# RICK_TNY_00.net
KiCad netlist of a schematic drawn in Altium Designer
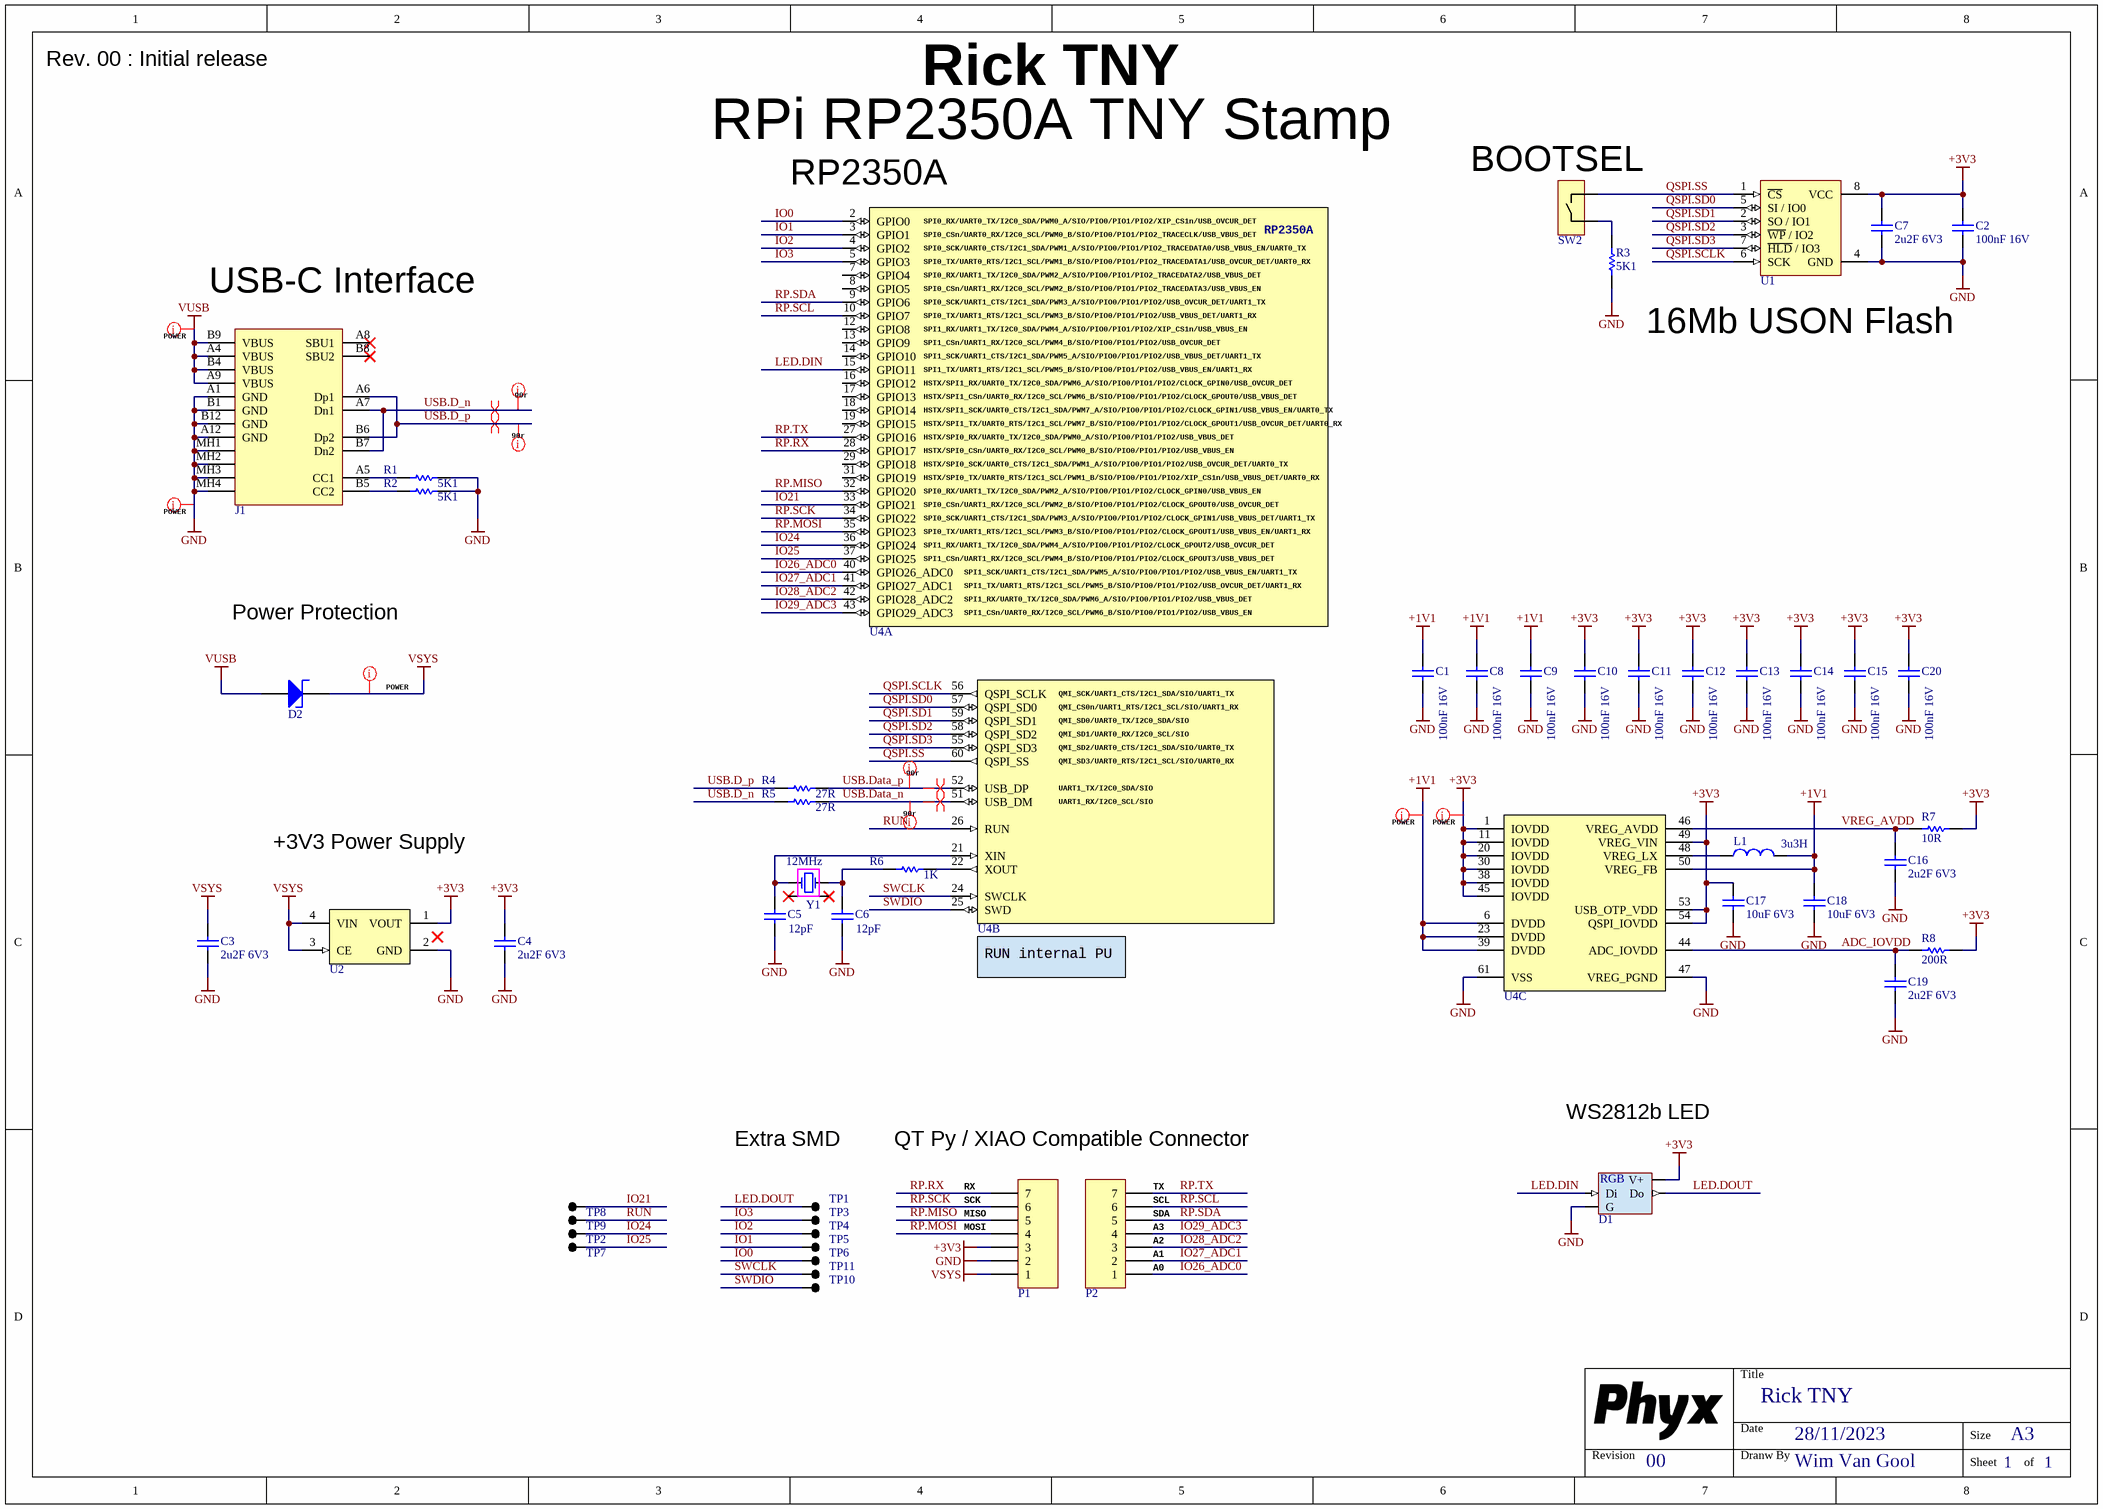
[diagram p0: RICK_TNY_00.SchDoc]

(export (version "E")
  (design (tool "Eeschema 10.0.6"))
  (components
    (comp (ref "C1")
      (value "100nF 16V")
      (footprint "C0402")
      (description "Capacitor Ceramic")
      (fields (field (name "Comment") "CAP_CERAMIC"))
      (libsource (lib "Phyx_Components") (part "CAP_CERAMIC"))
    )
    (comp (ref "C2")
      (value "100nF 16V")
      (footprint "C0402")
      (description "Capacitor Ceramic")
      (fields (field (name "Comment") "CAP_CERAMIC"))
      (libsource (lib "Phyx_Components") (part "CAP_CERAMIC"))
    )
    (comp (ref "C3")
      (value "2u2F 6V3")
      (footprint "C0402")
      (description "Capacitor Ceramic")
      (fields (field (name "Comment") "CAP_CERAMIC"))
      (libsource (lib "Phyx_Components") (part "CAP_CERAMIC"))
    )
    (comp (ref "C4")
      (value "2u2F 6V3")
      (footprint "C0402")
      (description "Capacitor Ceramic")
      (fields (field (name "Comment") "CAP_CERAMIC"))
      (libsource (lib "Phyx_Components") (part "CAP_CERAMIC"))
    )
    (comp (ref "C5")
      (value "12pF")
      (footprint "C0402")
      (description "CAP # 12pF 50V 0402")
      (fields (field (name "Comment") "CAP_CERAMIC"))
      (libsource (lib "Phyx_Components") (part "CAP_CERAMIC"))
    )
    (comp (ref "C6")
      (value "12pF")
      (footprint "C0402")
      (description "CAP # 12pF 50V 0402")
      (fields (field (name "Comment") "CAP_CERAMIC"))
      (libsource (lib "Phyx_Components") (part "CAP_CERAMIC"))
    )
    (comp (ref "C7")
      (value "2u2F 6V3")
      (footprint "C0402")
      (description "Capacitor Ceramic")
      (fields (field (name "Comment") "CAP_CERAMIC"))
      (libsource (lib "Phyx_Components") (part "CAP_CERAMIC"))
    )
    (comp (ref "C8")
      (value "100nF 16V")
      (footprint "C0402")
      (description "Capacitor Ceramic")
      (fields (field (name "Comment") "CAP_CERAMIC"))
      (libsource (lib "Phyx_Components") (part "CAP_CERAMIC"))
    )
    (comp (ref "C9")
      (value "100nF 16V")
      (footprint "C0402")
      (description "Capacitor Ceramic")
      (fields (field (name "Comment") "CAP_CERAMIC"))
      (libsource (lib "Phyx_Components") (part "CAP_CERAMIC"))
    )
    (comp (ref "C10")
      (value "100nF 16V")
      (footprint "C0402")
      (description "Capacitor Ceramic")
      (fields (field (name "Comment") "CAP_CERAMIC"))
      (libsource (lib "Phyx_Components") (part "CAP_CERAMIC"))
    )
    (comp (ref "C11")
      (value "100nF 16V")
      (footprint "C0402")
      (description "Capacitor Ceramic")
      (fields (field (name "Comment") "CAP_CERAMIC"))
      (libsource (lib "Phyx_Components") (part "CAP_CERAMIC"))
    )
    (comp (ref "C12")
      (value "100nF 16V")
      (footprint "C0402")
      (description "Capacitor Ceramic")
      (fields (field (name "Comment") "CAP_CERAMIC"))
      (libsource (lib "Phyx_Components") (part "CAP_CERAMIC"))
    )
    (comp (ref "C13")
      (value "100nF 16V")
      (footprint "C0402")
      (description "Capacitor Ceramic")
      (fields (field (name "Comment") "CAP_CERAMIC"))
      (libsource (lib "Phyx_Components") (part "CAP_CERAMIC"))
    )
    (comp (ref "C14")
      (value "100nF 16V")
      (footprint "C0402")
      (description "Capacitor Ceramic")
      (fields (field (name "Comment") "CAP_CERAMIC"))
      (libsource (lib "Phyx_Components") (part "CAP_CERAMIC"))
    )
    (comp (ref "C15")
      (value "100nF 16V")
      (footprint "C0402")
      (description "Capacitor Ceramic")
      (fields (field (name "Comment") "CAP_CERAMIC"))
      (libsource (lib "Phyx_Components") (part "CAP_CERAMIC"))
    )
    (comp (ref "C16")
      (value "2u2F 6V3")
      (footprint "C0402")
      (description "Capacitor Ceramic")
      (fields (field (name "Comment") "CAP_CERAMIC"))
      (libsource (lib "Phyx_Components") (part "CAP_CERAMIC"))
    )
    (comp (ref "C17")
      (value "10uF 6V3")
      (footprint "C0402")
      (description "Capacitor Ceramic")
      (fields (field (name "Comment") "CAP_CERAMIC"))
      (libsource (lib "Phyx_Components") (part "CAP_CERAMIC"))
    )
    (comp (ref "C18")
      (value "10uF 6V3")
      (footprint "C0402")
      (description "Capacitor Ceramic")
      (fields (field (name "Comment") "CAP_CERAMIC"))
      (libsource (lib "Phyx_Components") (part "CAP_CERAMIC"))
    )
    (comp (ref "C19")
      (value "2u2F 6V3")
      (footprint "C0402")
      (description "Capacitor Ceramic")
      (fields (field (name "Comment") "CAP_CERAMIC"))
      (libsource (lib "Phyx_Components") (part "CAP_CERAMIC"))
    )
    (comp (ref "C20")
      (value "100nF 16V")
      (footprint "C0402")
      (description "Capacitor Ceramic")
      (fields (field (name "Comment") "CAP_CERAMIC"))
      (libsource (lib "Phyx_Components") (part "CAP_CERAMIC"))
    )
    (comp (ref "D1")
      (value "WS2812 based digital RGB LED 1010 package")
      (footprint "LED_1010_WS2812B")
      (description "=Description")
      (libsource (lib "Phyx_Components") (part "LED_RGB_WS2812B_1010"))
    )
    (comp (ref "D2")
      (value "40V 1A 550mV@700mA 0603 Schottky")
      (footprint "ON_DSN2")
      (description "=Description")
      (libsource (lib "Phyx_Components") (part "Schottky_AC"))
    )
    (comp (ref "J1")
      (value "USB 2.0 C Reversible Receptacle Horizontal full SMD")
      (footprint "XUNPU-TYPEC-304S-ACP16")
      (libsource (lib "Phyx_Components") (part "USB_C_16_4"))
    )
    (comp (ref "L1")
      (value "3u3H")
      (footprint "L0805")
      (fields (field (name "Comment") "LQM21PN3R3MGRD"))
      (libsource (lib "Phyx_Components") (part "INDUCTOR"))
    )
    (comp (ref "P1") (value "Header 7") (footprint "HDR1X7") (libsource (lib "") (part "Header 7_1")))
    (comp (ref "P2")
      (value "Header 7")
      (footprint "HDR1X7")
      (libsource (lib "Phyx_Components") (part "Header 7"))
    )
    (comp (ref "R1")
      (value "5K1")
      (footprint "R0402")
      (fields (field (name "Comment") "RESISTOR"))
      (libsource (lib "Phyx_Components") (part "RESISTOR"))
    )
    (comp (ref "R2")
      (value "5K1")
      (footprint "R0402")
      (fields (field (name "Comment") "RESISTOR"))
      (libsource (lib "Phyx_Components") (part "RESISTOR"))
    )
    (comp (ref "R3")
      (value "5K1")
      (footprint "R0402")
      (fields (field (name "Comment") "RESISTOR"))
      (libsource (lib "Phyx_Components") (part "RESISTOR"))
    )
    (comp (ref "R4")
      (value "27R")
      (footprint "R0402")
      (fields (field (name "Comment") "RESISTOR"))
      (libsource (lib "Phyx_Components") (part "RESISTOR"))
    )
    (comp (ref "R5")
      (value "27R")
      (footprint "R0402")
      (fields (field (name "Comment") "RESISTOR"))
      (libsource (lib "Phyx_Components") (part "RESISTOR"))
    )
    (comp (ref "R6")
      (value "1K")
      (footprint "R0402")
      (fields (field (name "Comment") "RESISTOR"))
      (libsource (lib "Phyx_Components") (part "RESISTOR"))
    )
    (comp (ref "R7")
      (value "10R")
      (footprint "R0402")
      (fields (field (name "Comment") "RESISTOR"))
      (libsource (lib "Phyx_Components") (part "RESISTOR"))
    )
    (comp (ref "R8")
      (value "200R")
      (footprint "R0402")
      (fields (field (name "Comment") "RESISTOR"))
      (libsource (lib "Phyx_Components") (part "RESISTOR"))
    )
    (comp (ref "SW2")
      (value "TS24CA RA Tactile Switch 12V 50mA")
      (footprint "SHOU_HAN_TS24CA")
      (libsource (lib "Phyx_Components") (part "SW_TACT"))
    )
    (comp (ref "TP1")
      (value "TEST_PAD")
      (footprint "TP_0.4mm")
      (libsource (lib "Phyx_Components") (part "TEST_PAD"))
    )
    (comp (ref "TP2")
      (value "TEST_PAD")
      (footprint "TP_0.4mm")
      (libsource (lib "Phyx_Components") (part "TEST_PAD"))
    )
    (comp (ref "TP3")
      (value "TEST_PAD")
      (footprint "TP_0.4mm")
      (libsource (lib "Phyx_Components") (part "TEST_PAD"))
    )
    (comp (ref "TP4")
      (value "TEST_PAD")
      (footprint "TP_0.4mm")
      (libsource (lib "Phyx_Components") (part "TEST_PAD"))
    )
    (comp (ref "TP5")
      (value "TEST_PAD")
      (footprint "TP_0.4mm")
      (libsource (lib "Phyx_Components") (part "TEST_PAD"))
    )
    (comp (ref "TP6")
      (value "TEST_PAD")
      (footprint "TP_0.4mm")
      (libsource (lib "Phyx_Components") (part "TEST_PAD"))
    )
    (comp (ref "TP7")
      (value "TEST_PAD")
      (footprint "TP_0.4mm")
      (libsource (lib "Phyx_Components") (part "TEST_PAD"))
    )
    (comp (ref "TP8")
      (value "TEST_PAD")
      (footprint "TP_0.4mm")
      (libsource (lib "Phyx_Components") (part "TEST_PAD"))
    )
    (comp (ref "TP9")
      (value "TEST_PAD")
      (footprint "TP_0.4mm")
      (libsource (lib "Phyx_Components") (part "TEST_PAD"))
    )
    (comp (ref "TP10")
      (value "TEST_PAD")
      (footprint "TP_0.4mm")
      (libsource (lib "Phyx_Components") (part "TEST_PAD"))
    )
    (comp (ref "TP11")
      (value "TEST_PAD")
      (footprint "TP_0.4mm")
      (libsource (lib "Phyx_Components") (part "TEST_PAD"))
    )
    (comp (ref "U1")
      (value "16Mb 3V3 133MHz SPI Flash DFN2x3 GD25Q16EEIGR")
      (footprint "USON_8_0.5_2x3")
      (libsource (lib "Phyx_Components") (part "AT25SFxx"))
    )
    (comp (ref "U2")
      (value "3V3 LDO 500mA 150mV")
      (footprint "DFNWB_1.0x1.0")
      (description "=Designator")
      (libsource (lib "Phyx_Components") (part "LDO_OGEI"))
    )
    (comp (ref "U4")
      (value "RPi RP2350 QFN60 2xM33 ext Flash")
      (footprint "RPI_QFN60_0.4_7x7")
      (description "=Description")
      (libsource (lib "Phyx_Components") (part "RPI_RP2350A"))
    )
    (comp (ref "Y1")
      (value "12MHz")
      (footprint "XTAL_2520")
      (description "Crystal Oscillator 4pin casing")
      (fields (field (name "Comment") "12MHz 2520 12pF ±10ppm ±30ppm"))
      (libsource (lib "Phyx_Components") (part "XTAL_4"))
    )
  )
  (nets
    (net (code "1") (name "+1V1") (class "Default")
      (node (ref "C1") (pin "1") (pinfunction "1_1") (pintype "passive"))
      (node (ref "C18") (pin "1") (pinfunction "1_1") (pintype "passive"))
      (node (ref "C8") (pin "1") (pinfunction "1_1") (pintype "passive"))
      (node (ref "C9") (pin "1") (pinfunction "1_1") (pintype "passive"))
      (node (ref "L1") (pin "2") (pinfunction "2_2") (pintype "passive"))
      (node (ref "U4") (pin "23") (pinfunction "DVDD_23") (pintype "power_in"))
      (node (ref "U4") (pin "39") (pinfunction "DVDD_39") (pintype "power_in"))
      (node (ref "U4") (pin "50") (pinfunction "VREG_FB_50") (pintype "power_in"))
      (node (ref "U4") (pin "6") (pinfunction "DVDD_6") (pintype "power_in"))
    )
    (net (code "2") (name "+3V3") (class "Default")
      (node (ref "C10") (pin "1") (pinfunction "1_1") (pintype "passive"))
      (node (ref "C11") (pin "1") (pinfunction "1_1") (pintype "passive"))
      (node (ref "C12") (pin "1") (pinfunction "1_1") (pintype "passive"))
      (node (ref "C13") (pin "1") (pinfunction "1_1") (pintype "passive"))
      (node (ref "C14") (pin "1") (pinfunction "1_1") (pintype "passive"))
      (node (ref "C15") (pin "1") (pinfunction "1_1") (pintype "passive"))
      (node (ref "C17") (pin "1") (pinfunction "1_1") (pintype "passive"))
      (node (ref "C2") (pin "1") (pinfunction "1_1") (pintype "passive"))
      (node (ref "C20") (pin "1") (pinfunction "1_1") (pintype "passive"))
      (node (ref "C4") (pin "1") (pinfunction "1_1") (pintype "passive"))
      (node (ref "C7") (pin "1") (pinfunction "1_1") (pintype "passive"))
      (node (ref "D1") (pin "2") (pinfunction "V+_2") (pintype "power_in"))
      (node (ref "P1") (pin "3") (pinfunction "3_3") (pintype "passive"))
      (node (ref "R7") (pin "1") (pinfunction "1_1") (pintype "passive"))
      (node (ref "R8") (pin "1") (pinfunction "1_1") (pintype "passive"))
      (node (ref "U1") (pin "8") (pinfunction "VCC_8") (pintype "power_in"))
      (node (ref "U2") (pin "1") (pinfunction "VOUT_1") (pintype "power_in"))
      (node (ref "U4") (pin "1") (pinfunction "IOVDD_1") (pintype "power_in"))
      (node (ref "U4") (pin "11") (pinfunction "IOVDD_11") (pintype "power_in"))
      (node (ref "U4") (pin "20") (pinfunction "IOVDD_20") (pintype "power_in"))
      (node (ref "U4") (pin "30") (pinfunction "IOVDD_30") (pintype "power_in"))
      (node (ref "U4") (pin "38") (pinfunction "IOVDD_38") (pintype "power_in"))
      (node (ref "U4") (pin "45") (pinfunction "IOVDD_45") (pintype "power_in"))
      (node (ref "U4") (pin "49") (pinfunction "VREG_VIN_49") (pintype "power_in"))
      (node (ref "U4") (pin "53") (pinfunction "USB_OTP_VDD_53") (pintype "power_in"))
      (node (ref "U4") (pin "54") (pinfunction "QSPI_IOVDD_54") (pintype "power_in"))
    )
    (net (code "3") (name "/ADC_IOVDD") (class "Default")
      (node (ref "C19") (pin "1") (pinfunction "1_1") (pintype "passive"))
      (node (ref "R8") (pin "2") (pinfunction "2_2") (pintype "passive"))
      (node (ref "U4") (pin "44") (pinfunction "ADC_IOVDD_44") (pintype "power_in"))
    )
    (net (code "4") (name "/IO0") (class "Default")
      (node (ref "TP6") (pin "1") (pinfunction "1_1") (pintype "passive"))
      (node (ref "U4") (pin "2") (pinfunction "GPIO0_2") (pintype "bidirectional"))
    )
    (net (code "5") (name "/IO1") (class "Default")
      (node (ref "TP5") (pin "1") (pinfunction "1_1") (pintype "passive"))
      (node (ref "U4") (pin "3") (pinfunction "GPIO1_3") (pintype "bidirectional"))
    )
    (net (code "6") (name "/IO2") (class "Default")
      (node (ref "TP4") (pin "1") (pinfunction "1_1") (pintype "passive"))
      (node (ref "U4") (pin "4") (pinfunction "GPIO2_4") (pintype "bidirectional"))
    )
    (net (code "7") (name "/IO3") (class "Default")
      (node (ref "TP3") (pin "1") (pinfunction "1_1") (pintype "passive"))
      (node (ref "U4") (pin "5") (pinfunction "GPIO3_5") (pintype "bidirectional"))
    )
    (net (code "8") (name "/IO21") (class "Default")
      (node (ref "TP8") (pin "1") (pinfunction "1_1") (pintype "passive"))
      (node (ref "U4") (pin "33") (pinfunction "GPIO21_33") (pintype "bidirectional"))
    )
    (net (code "9") (name "/IO24") (class "Default")
      (node (ref "TP2") (pin "1") (pinfunction "1_1") (pintype "passive"))
      (node (ref "U4") (pin "36") (pinfunction "GPIO24_36") (pintype "bidirectional"))
    )
    (net (code "10") (name "/IO25") (class "Default")
      (node (ref "TP7") (pin "1") (pinfunction "1_1") (pintype "passive"))
      (node (ref "U4") (pin "37") (pinfunction "GPIO25_37") (pintype "bidirectional"))
    )
    (net (code "11") (name "/IO26_ADC0") (class "Default")
      (node (ref "P2") (pin "1") (pinfunction "1_1") (pintype "passive"))
      (node (ref "U4") (pin "40") (pinfunction "GPIO26_ADC0_40") (pintype "bidirectional"))
    )
    (net (code "12") (name "/IO27_ADC1") (class "Default")
      (node (ref "P2") (pin "2") (pinfunction "2_2") (pintype "passive"))
      (node (ref "U4") (pin "41") (pinfunction "GPIO27_ADC1_41") (pintype "bidirectional"))
    )
    (net (code "13") (name "/IO28_ADC2") (class "Default")
      (node (ref "P2") (pin "3") (pinfunction "3_3") (pintype "passive"))
      (node (ref "U4") (pin "42") (pinfunction "GPIO28_ADC2_42") (pintype "bidirectional"))
    )
    (net (code "14") (name "/IO29_ADC3") (class "Default")
      (node (ref "P2") (pin "4") (pinfunction "4_4") (pintype "passive"))
      (node (ref "U4") (pin "43") (pinfunction "GPIO29_ADC3_43") (pintype "bidirectional"))
    )
    (net (code "15") (name "/LED.DIN") (class "Default")
      (node (ref "D1") (pin "4") (pinfunction "Di_4") (pintype "input"))
      (node (ref "U4") (pin "15") (pinfunction "GPIO11_15") (pintype "bidirectional"))
    )
    (net (code "16") (name "/LED.DOUT") (class "Default")
      (node (ref "D1") (pin "1") (pinfunction "Do_1") (pintype "output"))
      (node (ref "TP1") (pin "1") (pinfunction "1_1") (pintype "passive"))
    )
    (net (code "17") (name "/QSPI.SCLK") (class "Default")
      (node (ref "U1") (pin "6") (pinfunction "SCK_6") (pintype "input"))
      (node (ref "U4") (pin "56") (pinfunction "QSPI_SCLK_56") (pintype "output"))
    )
    (net (code "18") (name "/QSPI.SD0") (class "Default")
      (node (ref "U1") (pin "5") (pinfunction "SI_/_IO0_5") (pintype "bidirectional"))
      (node (ref "U4") (pin "57") (pinfunction "QSPI_SD0_57") (pintype "bidirectional"))
    )
    (net (code "19") (name "/QSPI.SD1") (class "Default")
      (node (ref "U1") (pin "2") (pinfunction "SO_/_IO1_2") (pintype "bidirectional"))
      (node (ref "U4") (pin "59") (pinfunction "QSPI_SD1_59") (pintype "bidirectional"))
    )
    (net (code "20") (name "/QSPI.SD2") (class "Default")
      (node (ref "U1") (pin "3") (pinfunction "~{WP}_/_IO2_3") (pintype "bidirectional"))
      (node (ref "U4") (pin "58") (pinfunction "QSPI_SD2_58") (pintype "bidirectional"))
    )
    (net (code "21") (name "/QSPI.SD3") (class "Default")
      (node (ref "U1") (pin "7") (pinfunction "~{HLD}_/_IO3_7") (pintype "bidirectional"))
      (node (ref "U4") (pin "55") (pinfunction "QSPI_SD3_55") (pintype "bidirectional"))
    )
    (net (code "22") (name "/QSPI.SS") (class "Default")
      (node (ref "SW2") (pin "1") (pinfunction "1_1") (pintype "passive"))
      (node (ref "U1") (pin "1") (pinfunction "~{CS}_1") (pintype "input"))
      (node (ref "U4") (pin "60") (pinfunction "QSPI_SS_60") (pintype "output"))
    )
    (net (code "23") (name "/RP.MISO") (class "Default")
      (node (ref "P1") (pin "5") (pinfunction "5_5") (pintype "passive"))
      (node (ref "U4") (pin "32") (pinfunction "GPIO20_32") (pintype "bidirectional"))
    )
    (net (code "24") (name "/RP.MOSI") (class "Default")
      (node (ref "P1") (pin "4") (pinfunction "4_4") (pintype "passive"))
      (node (ref "U4") (pin "35") (pinfunction "GPIO23_35") (pintype "bidirectional"))
    )
    (net (code "25") (name "/RP.RX") (class "Default")
      (node (ref "P1") (pin "7") (pinfunction "7_7") (pintype "passive"))
      (node (ref "U4") (pin "28") (pinfunction "GPIO17_28") (pintype "bidirectional"))
    )
    (net (code "26") (name "/RP.SCK") (class "Default")
      (node (ref "P1") (pin "6") (pinfunction "6_6") (pintype "passive"))
      (node (ref "U4") (pin "34") (pinfunction "GPIO22_34") (pintype "bidirectional"))
    )
    (net (code "27") (name "/RP.SCL") (class "Default")
      (node (ref "P2") (pin "6") (pinfunction "6_6") (pintype "passive"))
      (node (ref "U4") (pin "10") (pinfunction "GPIO7_10") (pintype "bidirectional"))
    )
    (net (code "28") (name "/RP.SDA") (class "Default")
      (node (ref "P2") (pin "5") (pinfunction "5_5") (pintype "passive"))
      (node (ref "U4") (pin "9") (pinfunction "GPIO6_9") (pintype "bidirectional"))
    )
    (net (code "29") (name "/RP.TX") (class "Default")
      (node (ref "P2") (pin "7") (pinfunction "7_7") (pintype "passive"))
      (node (ref "U4") (pin "27") (pinfunction "GPIO16_27") (pintype "bidirectional"))
    )
    (net (code "30") (name "/RUN") (class "Default")
      (node (ref "TP9") (pin "1") (pinfunction "1_1") (pintype "passive"))
      (node (ref "U4") (pin "26") (pinfunction "RUN_26") (pintype "input"))
    )
    (net (code "31") (name "/SWCLK") (class "Default")
      (node (ref "TP11") (pin "1") (pinfunction "1_1") (pintype "passive"))
      (node (ref "U4") (pin "24") (pinfunction "SWCLK_24") (pintype "input"))
    )
    (net (code "32") (name "/SWDIO") (class "Default")
      (node (ref "TP10") (pin "1") (pinfunction "1_1") (pintype "passive"))
      (node (ref "U4") (pin "25") (pinfunction "SWD_25") (pintype "bidirectional"))
    )
    (net (code "33") (name "/USB.D_n") (class "Default")
      (node (ref "J1") (pin "A7") (pinfunction "Dn1_A7") (pintype "passive"))
      (node (ref "J1") (pin "B7") (pinfunction "Dn2_B7") (pintype "passive"))
      (node (ref "R5") (pin "2") (pinfunction "2_2") (pintype "passive"))
    )
    (net (code "34") (name "/USB.D_p") (class "Default")
      (node (ref "J1") (pin "A6") (pinfunction "Dp1_A6") (pintype "passive"))
      (node (ref "J1") (pin "B6") (pinfunction "Dp2_B6") (pintype "passive"))
      (node (ref "R4") (pin "2") (pinfunction "2_2") (pintype "passive"))
    )
    (net (code "35") (name "/USB.Data_n") (class "Default")
      (node (ref "R5") (pin "1") (pinfunction "1_1") (pintype "passive"))
      (node (ref "U4") (pin "51") (pinfunction "USB_DM_51") (pintype "bidirectional"))
    )
    (net (code "36") (name "/USB.Data_p") (class "Default")
      (node (ref "R4") (pin "1") (pinfunction "1_1") (pintype "passive"))
      (node (ref "U4") (pin "52") (pinfunction "USB_DP_52") (pintype "bidirectional"))
    )
    (net (code "37") (name "/VREG_AVDD") (class "Default")
      (node (ref "C16") (pin "1") (pinfunction "1_1") (pintype "passive"))
      (node (ref "R7") (pin "2") (pinfunction "2_2") (pintype "passive"))
      (node (ref "U4") (pin "46") (pinfunction "VREG_AVDD_46") (pintype "power_in"))
    )
    (net (code "38") (name "GND") (class "Default")
      (node (ref "C1") (pin "2") (pinfunction "2_2") (pintype "passive"))
      (node (ref "C10") (pin "2") (pinfunction "2_2") (pintype "passive"))
      (node (ref "C11") (pin "2") (pinfunction "2_2") (pintype "passive"))
      (node (ref "C12") (pin "2") (pinfunction "2_2") (pintype "passive"))
      (node (ref "C13") (pin "2") (pinfunction "2_2") (pintype "passive"))
      (node (ref "C14") (pin "2") (pinfunction "2_2") (pintype "passive"))
      (node (ref "C15") (pin "2") (pinfunction "2_2") (pintype "passive"))
      (node (ref "C16") (pin "2") (pinfunction "2_2") (pintype "passive"))
      (node (ref "C17") (pin "2") (pinfunction "2_2") (pintype "passive"))
      (node (ref "C18") (pin "2") (pinfunction "2_2") (pintype "passive"))
      (node (ref "C19") (pin "2") (pinfunction "2_2") (pintype "passive"))
      (node (ref "C2") (pin "2") (pinfunction "2_2") (pintype "passive"))
      (node (ref "C20") (pin "2") (pinfunction "2_2") (pintype "passive"))
      (node (ref "C3") (pin "2") (pinfunction "2_2") (pintype "passive"))
      (node (ref "C4") (pin "2") (pinfunction "2_2") (pintype "passive"))
      (node (ref "C5") (pin "2") (pinfunction "2_2") (pintype "passive"))
      (node (ref "C6") (pin "2") (pinfunction "2_2") (pintype "passive"))
      (node (ref "C7") (pin "2") (pinfunction "2_2") (pintype "passive"))
      (node (ref "C8") (pin "2") (pinfunction "2_2") (pintype "passive"))
      (node (ref "C9") (pin "2") (pinfunction "2_2") (pintype "passive"))
      (node (ref "D1") (pin "3") (pinfunction "G_3") (pintype "power_in"))
      (node (ref "J1") (pin "A1") (pinfunction "GND_A1") (pintype "passive"))
      (node (ref "J1") (pin "A12") (pinfunction "GND_A12") (pintype "passive"))
      (node (ref "J1") (pin "B1") (pinfunction "GND_B1") (pintype "passive"))
      (node (ref "J1") (pin "B12") (pinfunction "GND_B12") (pintype "passive"))
      (node (ref "J1") (pin "MH1") (pinfunction "Tab_MH1") (pintype "passive"))
      (node (ref "J1") (pin "MH2") (pinfunction "Tab_MH2") (pintype "passive"))
      (node (ref "J1") (pin "MH3") (pinfunction "Tab_MH3") (pintype "passive"))
      (node (ref "J1") (pin "MH4") (pinfunction "Tab_MH4") (pintype "passive"))
      (node (ref "P1") (pin "2") (pinfunction "2_2") (pintype "passive"))
      (node (ref "R1") (pin "1") (pinfunction "1_1") (pintype "passive"))
      (node (ref "R2") (pin "1") (pinfunction "1_1") (pintype "passive"))
      (node (ref "R3") (pin "2") (pinfunction "2_2") (pintype "passive"))
      (node (ref "U1") (pin "4") (pinfunction "GND_4") (pintype "power_in"))
      (node (ref "U2") (pin "2") (pinfunction "GND_2") (pintype "power_in"))
      (node (ref "U4") (pin "47") (pinfunction "VREG_PGND_47") (pintype "power_in"))
      (node (ref "U4") (pin "61") (pinfunction "VSS_61") (pintype "power_in"))
    )
    (net (code "39") (name "Net-(J1-CC1)") (class "Default")
      (node (ref "J1") (pin "A5") (pinfunction "CC1_A5") (pintype "passive"))
      (node (ref "R1") (pin "2") (pinfunction "2_2") (pintype "passive"))
    )
    (net (code "40") (name "Net-(J1-CC2)") (class "Default")
      (node (ref "J1") (pin "B5") (pinfunction "CC2_B5") (pintype "passive"))
      (node (ref "R2") (pin "2") (pinfunction "2_2") (pintype "passive"))
    )
    (net (code "41") (name "Net-(R3-Pad1)") (class "Default")
      (node (ref "R3") (pin "1") (pinfunction "1_1") (pintype "passive"))
      (node (ref "SW2") (pin "2") (pinfunction "2_2") (pintype "passive"))
    )
    (net (code "42") (name "Net-(U4B-XIN)") (class "Default")
      (node (ref "C5") (pin "1") (pinfunction "1_1") (pintype "passive"))
      (node (ref "U4") (pin "21") (pinfunction "XIN_21") (pintype "input"))
      (node (ref "Y1") (pin "1") (pinfunction "OSC1_1") (pintype "passive"))
    )
    (net (code "43") (name "Net-(U4B-XOUT)") (class "Default")
      (node (ref "R6") (pin "2") (pinfunction "2_2") (pintype "passive"))
      (node (ref "U4") (pin "22") (pinfunction "XOUT_22") (pintype "output"))
    )
    (net (code "44") (name "Net-(U4C-VREG_LX)") (class "Default")
      (node (ref "L1") (pin "1") (pinfunction "1_1") (pintype "passive"))
      (node (ref "U4") (pin "48") (pinfunction "VREG_LX_48") (pintype "power_in"))
    )
    (net (code "45") (name "Net-(Y1-OSC3)") (class "Default")
      (node (ref "C6") (pin "1") (pinfunction "1_1") (pintype "passive"))
      (node (ref "R6") (pin "1") (pinfunction "1_1") (pintype "passive"))
      (node (ref "Y1") (pin "3") (pinfunction "OSC3_3") (pintype "passive"))
    )
    (net (code "46") (name "VSYS") (class "Default")
      (node (ref "C3") (pin "1") (pinfunction "1_1") (pintype "passive"))
      (node (ref "D2") (pin "C") (pinfunction "C_C") (pintype "passive"))
      (node (ref "P1") (pin "1") (pinfunction "1_1") (pintype "passive"))
      (node (ref "U2") (pin "3") (pinfunction "CE_3") (pintype "input"))
      (node (ref "U2") (pin "4") (pinfunction "VIN_4") (pintype "power_in"))
    )
    (net (code "47") (name "VUSB") (class "Default")
      (node (ref "D2") (pin "A") (pinfunction "A_A") (pintype "passive"))
      (node (ref "J1") (pin "A4") (pinfunction "VBUS_A4") (pintype "passive"))
      (node (ref "J1") (pin "A9") (pinfunction "VBUS_A9") (pintype "passive"))
      (node (ref "J1") (pin "B4") (pinfunction "VBUS_B4") (pintype "passive"))
      (node (ref "J1") (pin "B9") (pinfunction "VBUS_B9") (pintype "passive"))
    )
    (net (code "48") (name "unconnected-(J1-SBU1-PadA8)") (class "Default")
      (node (ref "J1") (pin "A8") (pinfunction "SBU1_A8") (pintype "passive+no_connect"))
    )
    (net (code "49") (name "unconnected-(J1-SBU2-PadB8)") (class "Default")
      (node (ref "J1") (pin "B8") (pinfunction "SBU2_B8") (pintype "passive+no_connect"))
    )
    (net (code "50") (name "unconnected-(U4A-GPIO4-Pad7)") (class "Default")
      (node (ref "U4") (pin "7") (pinfunction "GPIO4_7") (pintype "bidirectional"))
    )
    (net (code "51") (name "unconnected-(U4A-GPIO5-Pad8)") (class "Default")
      (node (ref "U4") (pin "8") (pinfunction "GPIO5_8") (pintype "bidirectional"))
    )
    (net (code "52") (name "unconnected-(U4A-GPIO8-Pad12)") (class "Default")
      (node (ref "U4") (pin "12") (pinfunction "GPIO8_12") (pintype "bidirectional"))
    )
    (net (code "53") (name "unconnected-(U4A-GPIO9-Pad13)") (class "Default")
      (node (ref "U4") (pin "13") (pinfunction "GPIO9_13") (pintype "bidirectional"))
    )
    (net (code "54") (name "unconnected-(U4A-GPIO10-Pad14)") (class "Default")
      (node (ref "U4") (pin "14") (pinfunction "GPIO10_14") (pintype "bidirectional"))
    )
    (net (code "55") (name "unconnected-(U4A-GPIO12-Pad16)") (class "Default")
      (node (ref "U4") (pin "16") (pinfunction "GPIO12_16") (pintype "bidirectional"))
    )
    (net (code "56") (name "unconnected-(U4A-GPIO13-Pad17)") (class "Default")
      (node (ref "U4") (pin "17") (pinfunction "GPIO13_17") (pintype "bidirectional"))
    )
    (net (code "57") (name "unconnected-(U4A-GPIO14-Pad18)") (class "Default")
      (node (ref "U4") (pin "18") (pinfunction "GPIO14_18") (pintype "bidirectional"))
    )
    (net (code "58") (name "unconnected-(U4A-GPIO15-Pad19)") (class "Default")
      (node (ref "U4") (pin "19") (pinfunction "GPIO15_19") (pintype "bidirectional"))
    )
    (net (code "59") (name "unconnected-(U4A-GPIO18-Pad29)") (class "Default")
      (node (ref "U4") (pin "29") (pinfunction "GPIO18_29") (pintype "bidirectional"))
    )
    (net (code "60") (name "unconnected-(U4A-GPIO19-Pad31)") (class "Default")
      (node (ref "U4") (pin "31") (pinfunction "GPIO19_31") (pintype "bidirectional"))
    )
    (net (code "61") (name "unconnected-(Y1-GND1-Pad2)") (class "Default")
      (node (ref "Y1") (pin "2") (pinfunction "GND1_2") (pintype "power_in+no_connect"))
    )
    (net (code "62") (name "unconnected-(Y1-GND2-Pad4)") (class "Default")
      (node (ref "Y1") (pin "4") (pinfunction "GND2_4") (pintype "power_in+no_connect"))
    )
  )
)
